# 24V_Regulator.net
KiCad netlist of a schematic drawn in Altium Designer
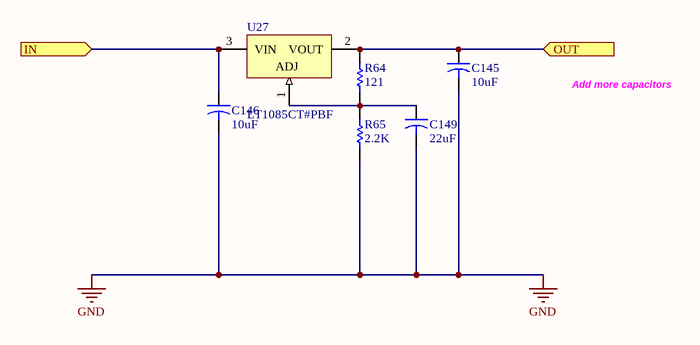
[diagram p0: 24V_Regulator.SchDoc]

(export (version "E")
  (design (tool "Eeschema 10.0.6"))
  (components
    (comp (ref "C145")
      (value "10uF")
      (footprint "Tantalum_2917")
      (description "Capacitor, 100uF NICHICON")
      (libsource (lib "Arturo_Approved") (part "UVR1V102MHD1TO"))
    )
    (comp (ref "C146")
      (value "10uF")
      (footprint "Tantalum_2917")
      (description "Capacitor, 100uF NICHICON")
      (libsource (lib "Arturo_Approved") (part "UVR1V102MHD1TO"))
    )
    (comp (ref "C149")
      (value "22uF")
      (footprint "Tantalum_2917")
      (description "Capacitor, 100uF NICHICON")
      (libsource (lib "Arturo_Approved") (part "UVR1V102MHD1TO"))
    )
    (comp (ref "R64")
      (value "121")
      (footprint "2512_SMD")
      (description "100K 1% 1/10W")
      (libsource (lib "Arturo_Approved") (part "RR1220P-104-D"))
    )
    (comp (ref "R65")
      (value "2.2K")
      (footprint "2512_SMD")
      (description "100K 1% 1/10W")
      (libsource (lib "Arturo_Approved") (part "RR1220P-104-D"))
    )
    (comp (ref "U27")
      (value "LT1085CT#PBF")
      (footprint "LT-T-3")
      (fields (field (name "MANUFACTURER") "Linear Technology"))
      (libsource (lib "Altium Content Vault") (part "LT-LT1XXXX"))
    )
  )
  (nets
    (net (code "1") (name "/IN") (class "Default")
      (node (ref "C146") (pin "1") (pinfunction "1_1") (pintype "passive"))
      (node (ref "U27") (pin "3") (pinfunction "VIN_3") (pintype "power_in"))
    )
    (net (code "2") (name "/OUT") (class "Default")
      (node (ref "C145") (pin "1") (pinfunction "1_1") (pintype "passive"))
      (node (ref "R64") (pin "2") (pinfunction "2_2") (pintype "passive"))
      (node (ref "U27") (pin "2") (pinfunction "VOUT_2") (pintype "power_in"))
    )
    (net (code "3") (name "GND") (class "Default")
      (node (ref "C145") (pin "2") (pinfunction "2_2") (pintype "passive"))
      (node (ref "C146") (pin "2") (pinfunction "2_2") (pintype "passive"))
      (node (ref "C149") (pin "2") (pinfunction "2_2") (pintype "passive"))
      (node (ref "R65") (pin "1") (pinfunction "1_1") (pintype "passive"))
    )
    (net (code "4") (name "Net-(U27-ADJ)") (class "Default")
      (node (ref "C149") (pin "1") (pinfunction "1_1") (pintype "passive"))
      (node (ref "R64") (pin "1") (pinfunction "1_1") (pintype "passive"))
      (node (ref "R65") (pin "2") (pinfunction "2_2") (pintype "passive"))
      (node (ref "U27") (pin "1") (pinfunction "ADJ_1") (pintype "input"))
    )
  )
)
